# 7953_IDC_TO_RS.net
KiCad netlist of a schematic drawn in Altium Designer
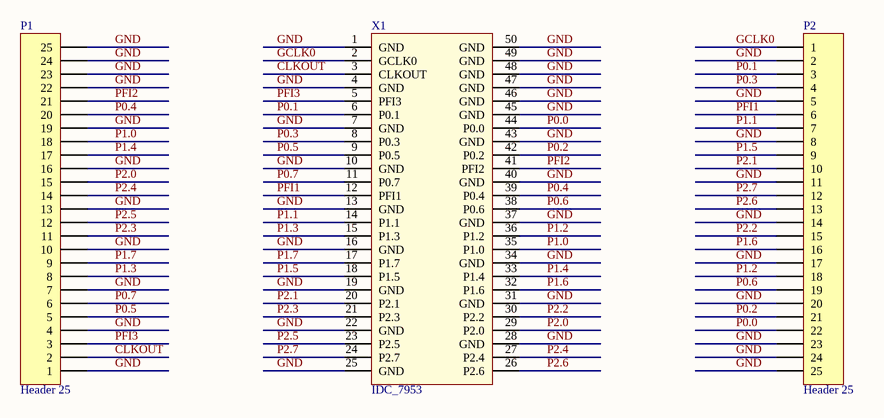
[diagram p0: 7953_IDC_TO_RS.SchDoc]

(export (version "E")
  (design (tool "Eeschema 10.0.6"))
  (components
    (comp (ref "P1")
      (value "Header 25")
      (footprint "HDR1X25")
      (description "Header, 25-Pin")
      (fields (field (name "PUBLISHER") "Altium Limited"))
      (libsource (lib "Miscellaneous Connectors") (part "Header 25"))
    )
    (comp (ref "P2")
      (value "Header 25")
      (footprint "HDR1X25")
      (description "Header, 25-Pin")
      (fields (field (name "PUBLISHER") "Altium Limited"))
      (libsource (lib "") (part "Header 25_1"))
    )
    (comp (ref "X1") (value "IDC_7953") (footprint "IDC_DIO") (libsource (lib "VPL") (part "IDC_7953")))
  )
  (nets
    (net (code "1") (name "/CLKOUT") (class "Default")
      (node (ref "P1") (pin "2") (pinfunction "2_2") (pintype "passive"))
      (node (ref "X1") (pin "3") (pinfunction "CLKOUT_3") (pintype "passive"))
    )
    (net (code "2") (name "/GCLK0") (class "Default")
      (node (ref "P2") (pin "1") (pinfunction "1_1") (pintype "passive"))
      (node (ref "X1") (pin "2") (pinfunction "GCLK0_2") (pintype "passive"))
    )
    (net (code "3") (name "/GND") (class "Default")
      (node (ref "P1") (pin "1") (pinfunction "1_1") (pintype "passive"))
      (node (ref "P1") (pin "10") (pinfunction "10_10") (pintype "passive"))
      (node (ref "P1") (pin "13") (pinfunction "13_13") (pintype "passive"))
      (node (ref "P1") (pin "16") (pinfunction "16_16") (pintype "passive"))
      (node (ref "P1") (pin "19") (pinfunction "19_19") (pintype "passive"))
      (node (ref "P1") (pin "22") (pinfunction "22_22") (pintype "passive"))
      (node (ref "P1") (pin "23") (pinfunction "23_23") (pintype "passive"))
      (node (ref "P1") (pin "24") (pinfunction "24_24") (pintype "passive"))
      (node (ref "P1") (pin "25") (pinfunction "25_25") (pintype "passive"))
      (node (ref "P1") (pin "4") (pinfunction "4_4") (pintype "passive"))
      (node (ref "P1") (pin "7") (pinfunction "7_7") (pintype "passive"))
      (node (ref "P2") (pin "11") (pinfunction "11_11") (pintype "passive"))
      (node (ref "P2") (pin "14") (pinfunction "14_14") (pintype "passive"))
      (node (ref "P2") (pin "17") (pinfunction "17_17") (pintype "passive"))
      (node (ref "P2") (pin "2") (pinfunction "2_2") (pintype "passive"))
      (node (ref "P2") (pin "20") (pinfunction "20_20") (pintype "passive"))
      (node (ref "P2") (pin "23") (pinfunction "23_23") (pintype "passive"))
      (node (ref "P2") (pin "24") (pinfunction "24_24") (pintype "passive"))
      (node (ref "P2") (pin "25") (pinfunction "25_25") (pintype "passive"))
      (node (ref "P2") (pin "5") (pinfunction "5_5") (pintype "passive"))
      (node (ref "P2") (pin "8") (pinfunction "8_8") (pintype "passive"))
      (node (ref "X1") (pin "1") (pinfunction "GND_1") (pintype "passive"))
      (node (ref "X1") (pin "10") (pinfunction "GND_10") (pintype "passive"))
      (node (ref "X1") (pin "13") (pinfunction "GND_13") (pintype "passive"))
      (node (ref "X1") (pin "16") (pinfunction "GND_16") (pintype "passive"))
      (node (ref "X1") (pin "19") (pinfunction "GND_19") (pintype "passive"))
      (node (ref "X1") (pin "22") (pinfunction "GND_22") (pintype "passive"))
      (node (ref "X1") (pin "25") (pinfunction "GND_25") (pintype "passive"))
      (node (ref "X1") (pin "28") (pinfunction "GND_28") (pintype "passive"))
      (node (ref "X1") (pin "31") (pinfunction "GND_31") (pintype "passive"))
      (node (ref "X1") (pin "34") (pinfunction "GND_34") (pintype "passive"))
      (node (ref "X1") (pin "37") (pinfunction "GND_37") (pintype "passive"))
      (node (ref "X1") (pin "4") (pinfunction "GND_4") (pintype "passive"))
      (node (ref "X1") (pin "40") (pinfunction "GND_40") (pintype "passive"))
      (node (ref "X1") (pin "43") (pinfunction "GND_43") (pintype "passive"))
      (node (ref "X1") (pin "45") (pinfunction "GND_45") (pintype "passive"))
      (node (ref "X1") (pin "46") (pinfunction "GND_46") (pintype "passive"))
      (node (ref "X1") (pin "47") (pinfunction "GND_47") (pintype "passive"))
      (node (ref "X1") (pin "48") (pinfunction "GND_48") (pintype "passive"))
      (node (ref "X1") (pin "49") (pinfunction "GND_49") (pintype "passive"))
      (node (ref "X1") (pin "50") (pinfunction "GND_50") (pintype "passive"))
      (node (ref "X1") (pin "7") (pinfunction "GND_7") (pintype "passive"))
    )
    (net (code "4") (name "/P0.0") (class "Default")
      (node (ref "P2") (pin "22") (pinfunction "22_22") (pintype "passive"))
      (node (ref "X1") (pin "44") (pinfunction "P0.0_44") (pintype "passive"))
    )
    (net (code "5") (name "/P0.1") (class "Default")
      (node (ref "P2") (pin "3") (pinfunction "3_3") (pintype "passive"))
      (node (ref "X1") (pin "6") (pinfunction "P0.1_6") (pintype "passive"))
    )
    (net (code "6") (name "/P0.2") (class "Default")
      (node (ref "P2") (pin "21") (pinfunction "21_21") (pintype "passive"))
      (node (ref "X1") (pin "42") (pinfunction "P0.2_42") (pintype "passive"))
    )
    (net (code "7") (name "/P0.3") (class "Default")
      (node (ref "P2") (pin "4") (pinfunction "4_4") (pintype "passive"))
      (node (ref "X1") (pin "8") (pinfunction "P0.3_8") (pintype "passive"))
    )
    (net (code "8") (name "/P0.4") (class "Default")
      (node (ref "P1") (pin "20") (pinfunction "20_20") (pintype "passive"))
      (node (ref "X1") (pin "39") (pinfunction "P0.4_39") (pintype "passive"))
    )
    (net (code "9") (name "/P0.5") (class "Default")
      (node (ref "P1") (pin "5") (pinfunction "5_5") (pintype "passive"))
      (node (ref "X1") (pin "9") (pinfunction "P0.5_9") (pintype "passive"))
    )
    (net (code "10") (name "/P0.6") (class "Default")
      (node (ref "P2") (pin "19") (pinfunction "19_19") (pintype "passive"))
      (node (ref "X1") (pin "38") (pinfunction "P0.6_38") (pintype "passive"))
    )
    (net (code "11") (name "/P0.7") (class "Default")
      (node (ref "P1") (pin "6") (pinfunction "6_6") (pintype "passive"))
      (node (ref "X1") (pin "11") (pinfunction "P0.7_11") (pintype "passive"))
    )
    (net (code "12") (name "/P1.0") (class "Default")
      (node (ref "P1") (pin "18") (pinfunction "18_18") (pintype "passive"))
      (node (ref "X1") (pin "35") (pinfunction "P1.0_35") (pintype "passive"))
    )
    (net (code "13") (name "/P1.1") (class "Default")
      (node (ref "P2") (pin "7") (pinfunction "7_7") (pintype "passive"))
      (node (ref "X1") (pin "14") (pinfunction "P1.1_14") (pintype "passive"))
    )
    (net (code "14") (name "/P1.2") (class "Default")
      (node (ref "P2") (pin "18") (pinfunction "18_18") (pintype "passive"))
      (node (ref "X1") (pin "36") (pinfunction "P1.2_36") (pintype "passive"))
    )
    (net (code "15") (name "/P1.3") (class "Default")
      (node (ref "P1") (pin "8") (pinfunction "8_8") (pintype "passive"))
      (node (ref "X1") (pin "15") (pinfunction "P1.3_15") (pintype "passive"))
    )
    (net (code "16") (name "/P1.4") (class "Default")
      (node (ref "P1") (pin "17") (pinfunction "17_17") (pintype "passive"))
      (node (ref "X1") (pin "33") (pinfunction "P1.4_33") (pintype "passive"))
    )
    (net (code "17") (name "/P1.5") (class "Default")
      (node (ref "P2") (pin "9") (pinfunction "9_9") (pintype "passive"))
      (node (ref "X1") (pin "18") (pinfunction "P1.5_18") (pintype "passive"))
    )
    (net (code "18") (name "/P1.6") (class "Default")
      (node (ref "P2") (pin "16") (pinfunction "16_16") (pintype "passive"))
      (node (ref "X1") (pin "32") (pinfunction "P1.6_32") (pintype "passive"))
    )
    (net (code "19") (name "/P1.7") (class "Default")
      (node (ref "P1") (pin "9") (pinfunction "9_9") (pintype "passive"))
      (node (ref "X1") (pin "17") (pinfunction "P1.7_17") (pintype "passive"))
    )
    (net (code "20") (name "/P2.0") (class "Default")
      (node (ref "P1") (pin "15") (pinfunction "15_15") (pintype "passive"))
      (node (ref "X1") (pin "29") (pinfunction "P2.0_29") (pintype "passive"))
    )
    (net (code "21") (name "/P2.1") (class "Default")
      (node (ref "P2") (pin "10") (pinfunction "10_10") (pintype "passive"))
      (node (ref "X1") (pin "20") (pinfunction "P2.1_20") (pintype "passive"))
    )
    (net (code "22") (name "/P2.2") (class "Default")
      (node (ref "P2") (pin "15") (pinfunction "15_15") (pintype "passive"))
      (node (ref "X1") (pin "30") (pinfunction "P2.2_30") (pintype "passive"))
    )
    (net (code "23") (name "/P2.3") (class "Default")
      (node (ref "P1") (pin "11") (pinfunction "11_11") (pintype "passive"))
      (node (ref "X1") (pin "21") (pinfunction "P2.3_21") (pintype "passive"))
    )
    (net (code "24") (name "/P2.4") (class "Default")
      (node (ref "P1") (pin "14") (pinfunction "14_14") (pintype "passive"))
      (node (ref "X1") (pin "27") (pinfunction "P2.4_27") (pintype "passive"))
    )
    (net (code "25") (name "/P2.5") (class "Default")
      (node (ref "P1") (pin "12") (pinfunction "12_12") (pintype "passive"))
      (node (ref "X1") (pin "23") (pinfunction "P2.5_23") (pintype "passive"))
    )
    (net (code "26") (name "/P2.6") (class "Default")
      (node (ref "P2") (pin "13") (pinfunction "13_13") (pintype "passive"))
      (node (ref "X1") (pin "26") (pinfunction "P2.6_26") (pintype "passive"))
    )
    (net (code "27") (name "/P2.7") (class "Default")
      (node (ref "P2") (pin "12") (pinfunction "12_12") (pintype "passive"))
      (node (ref "X1") (pin "24") (pinfunction "P2.7_24") (pintype "passive"))
    )
    (net (code "28") (name "/PFI1") (class "Default")
      (node (ref "P2") (pin "6") (pinfunction "6_6") (pintype "passive"))
      (node (ref "X1") (pin "12") (pinfunction "PFI1_12") (pintype "passive"))
    )
    (net (code "29") (name "/PFI2") (class "Default")
      (node (ref "P1") (pin "21") (pinfunction "21_21") (pintype "passive"))
      (node (ref "X1") (pin "41") (pinfunction "PFI2_41") (pintype "passive"))
    )
    (net (code "30") (name "/PFI3") (class "Default")
      (node (ref "P1") (pin "3") (pinfunction "3_3") (pintype "passive"))
      (node (ref "X1") (pin "5") (pinfunction "PFI3_5") (pintype "passive"))
    )
  )
)
